# port_adaptor_1_2.net
KiCad netlist of a schematic drawn in EAGLE
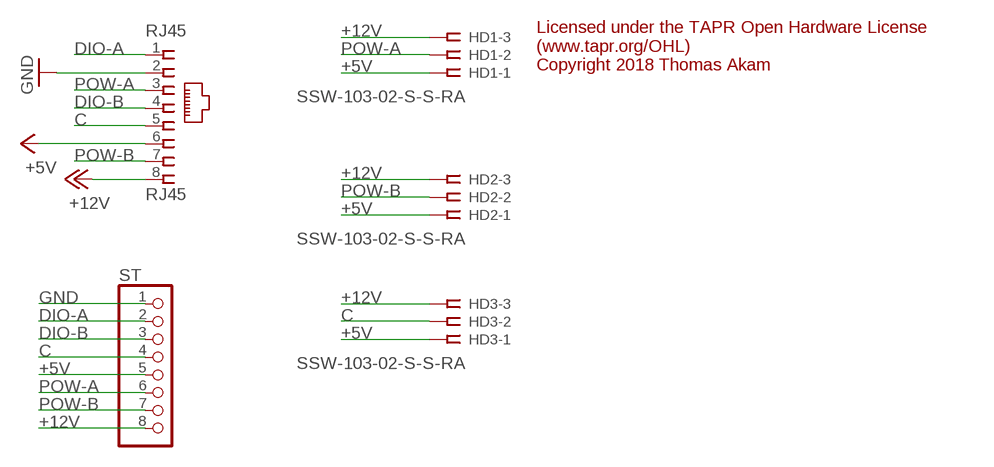
[diagram p0: schematic, sheet 1]

(export (version "E")
  (design (tool "Eeschema 10.0.6"))
  (components
    (comp (ref "HD1")
      (value "SSW-103-02-S-S-RA")
      (footprint "eagle-import:SSW-103-02-S-S-RA")
      (libsource (lib "eagle-import") (part "SSW-103-02-S-S-RA"))
    )
    (comp (ref "HD2")
      (value "SSW-103-02-S-S-RA")
      (footprint "eagle-import:SSW-103-02-S-S-RA")
      (libsource (lib "eagle-import") (part "SSW-103-02-S-S-RA"))
    )
    (comp (ref "HD3")
      (value "SSW-103-02-S-S-RA")
      (footprint "eagle-import:SSW-103-02-S-S-RA")
      (libsource (lib "eagle-import") (part "SSW-103-02-S-S-RA"))
    )
    (comp (ref "RJ45")
      (value "RJ45")
      (footprint "eagle-import:RJ45-NO-SHIELD-VERTICAL")
      (libsource (lib "eagle-import") (part "RJ45VERTICAL"))
    )
    (comp (ref "ST")
      (value "PINHD-1X8")
      (footprint "eagle-import:1X08")
      (libsource (lib "eagle-import") (part "PINHD-1X8"))
    )
  )
  (nets
    (net (code "1") (name "+5V") (class "Default")
      (node (ref "HD1") (pin "1") (pinfunction "1_1") (pintype "passive"))
      (node (ref "HD2") (pin "1") (pinfunction "1_1") (pintype "passive"))
      (node (ref "HD3") (pin "1") (pinfunction "1_1") (pintype "passive"))
      (node (ref "RJ45") (pin "6") (pinfunction "6_6") (pintype "passive"))
      (node (ref "ST") (pin "5") (pinfunction "5_5") (pintype "passive"))
    )
    (net (code "2") (name "+12V") (class "Default")
      (node (ref "HD1") (pin "3") (pinfunction "1_3") (pintype "passive"))
      (node (ref "HD2") (pin "3") (pinfunction "1_3") (pintype "passive"))
      (node (ref "HD3") (pin "3") (pinfunction "1_3") (pintype "passive"))
      (node (ref "RJ45") (pin "8") (pinfunction "8_8") (pintype "passive"))
      (node (ref "ST") (pin "8") (pinfunction "8_8") (pintype "passive"))
    )
    (net (code "3") (name "/C") (class "Default")
      (node (ref "HD3") (pin "2") (pinfunction "1_2") (pintype "passive"))
      (node (ref "RJ45") (pin "5") (pinfunction "5_5") (pintype "passive"))
      (node (ref "ST") (pin "4") (pinfunction "4_4") (pintype "passive"))
    )
    (net (code "4") (name "/DIO-A") (class "Default")
      (node (ref "RJ45") (pin "1") (pinfunction "1_1") (pintype "passive"))
      (node (ref "ST") (pin "2") (pinfunction "2_2") (pintype "passive"))
    )
    (net (code "5") (name "/DIO-B") (class "Default")
      (node (ref "RJ45") (pin "4") (pinfunction "4_4") (pintype "passive"))
      (node (ref "ST") (pin "3") (pinfunction "3_3") (pintype "passive"))
    )
    (net (code "6") (name "/POW-A") (class "Default")
      (node (ref "HD1") (pin "2") (pinfunction "1_2") (pintype "passive"))
      (node (ref "RJ45") (pin "3") (pinfunction "3_3") (pintype "passive"))
      (node (ref "ST") (pin "6") (pinfunction "6_6") (pintype "passive"))
    )
    (net (code "7") (name "/POW-B") (class "Default")
      (node (ref "HD2") (pin "2") (pinfunction "1_2") (pintype "passive"))
      (node (ref "RJ45") (pin "7") (pinfunction "7_7") (pintype "passive"))
      (node (ref "ST") (pin "7") (pinfunction "7_7") (pintype "passive"))
    )
    (net (code "8") (name "GND") (class "Default")
      (node (ref "RJ45") (pin "2") (pinfunction "2_2") (pintype "passive"))
      (node (ref "ST") (pin "1") (pinfunction "1_1") (pintype "passive"))
    )
  )
)
